# Lab_Controller_Board_v05.net
KiCad netlist of a schematic drawn in EAGLE
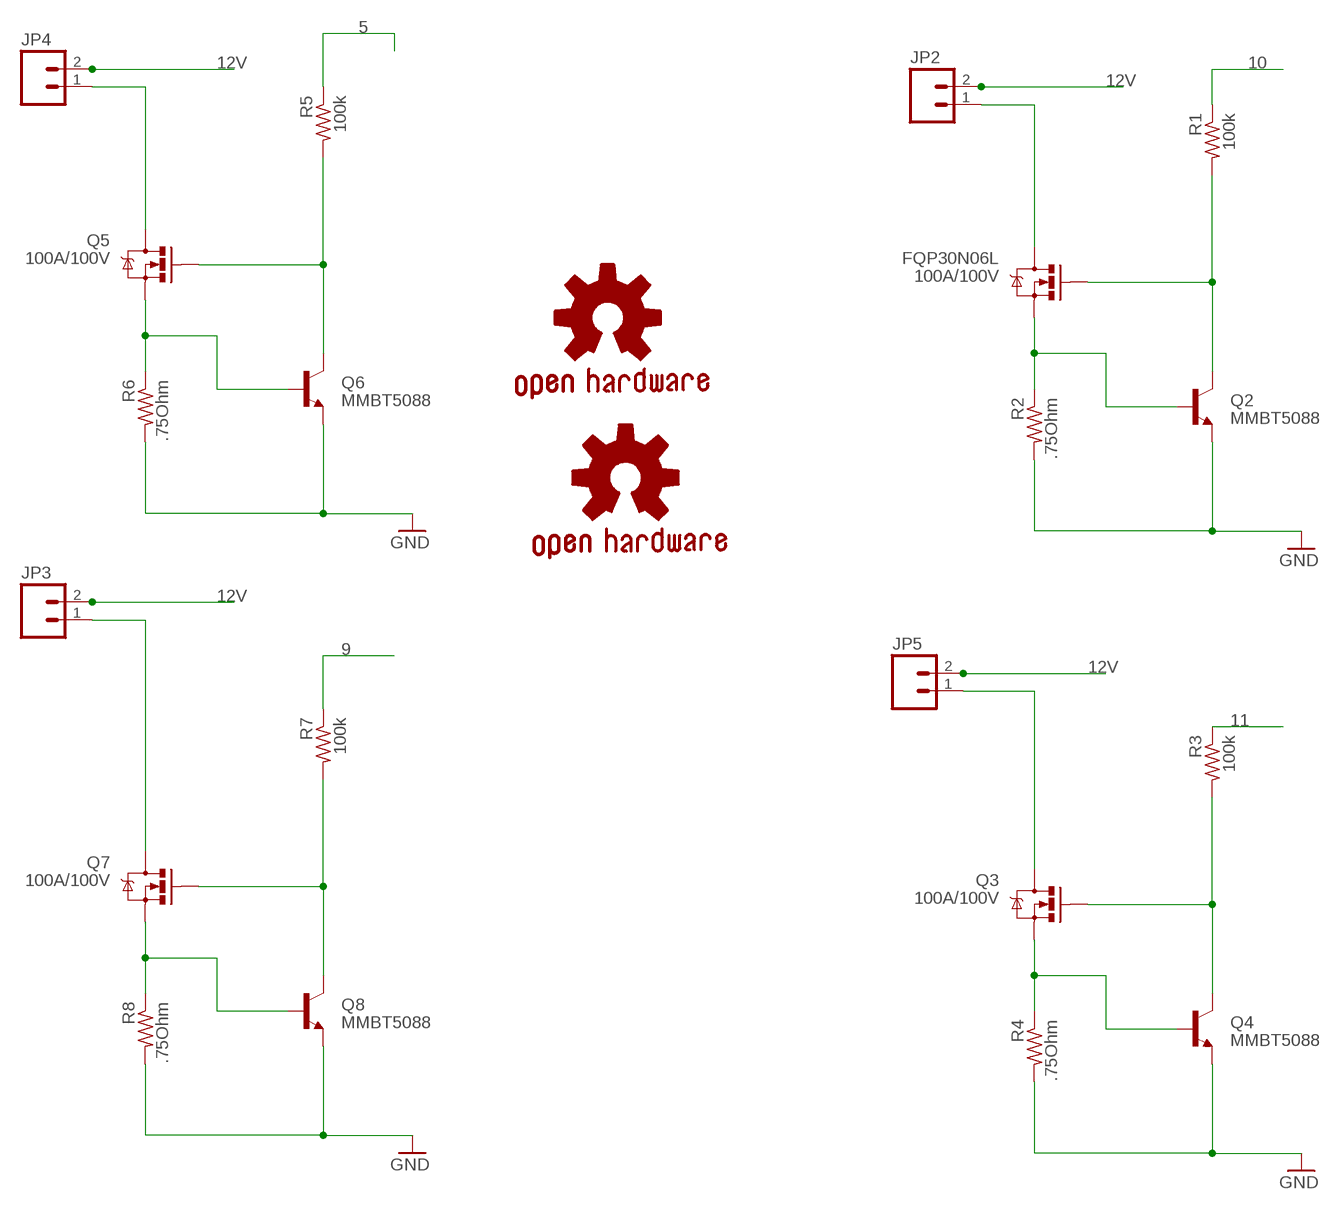
[diagram p0: schematic, sheet 1]
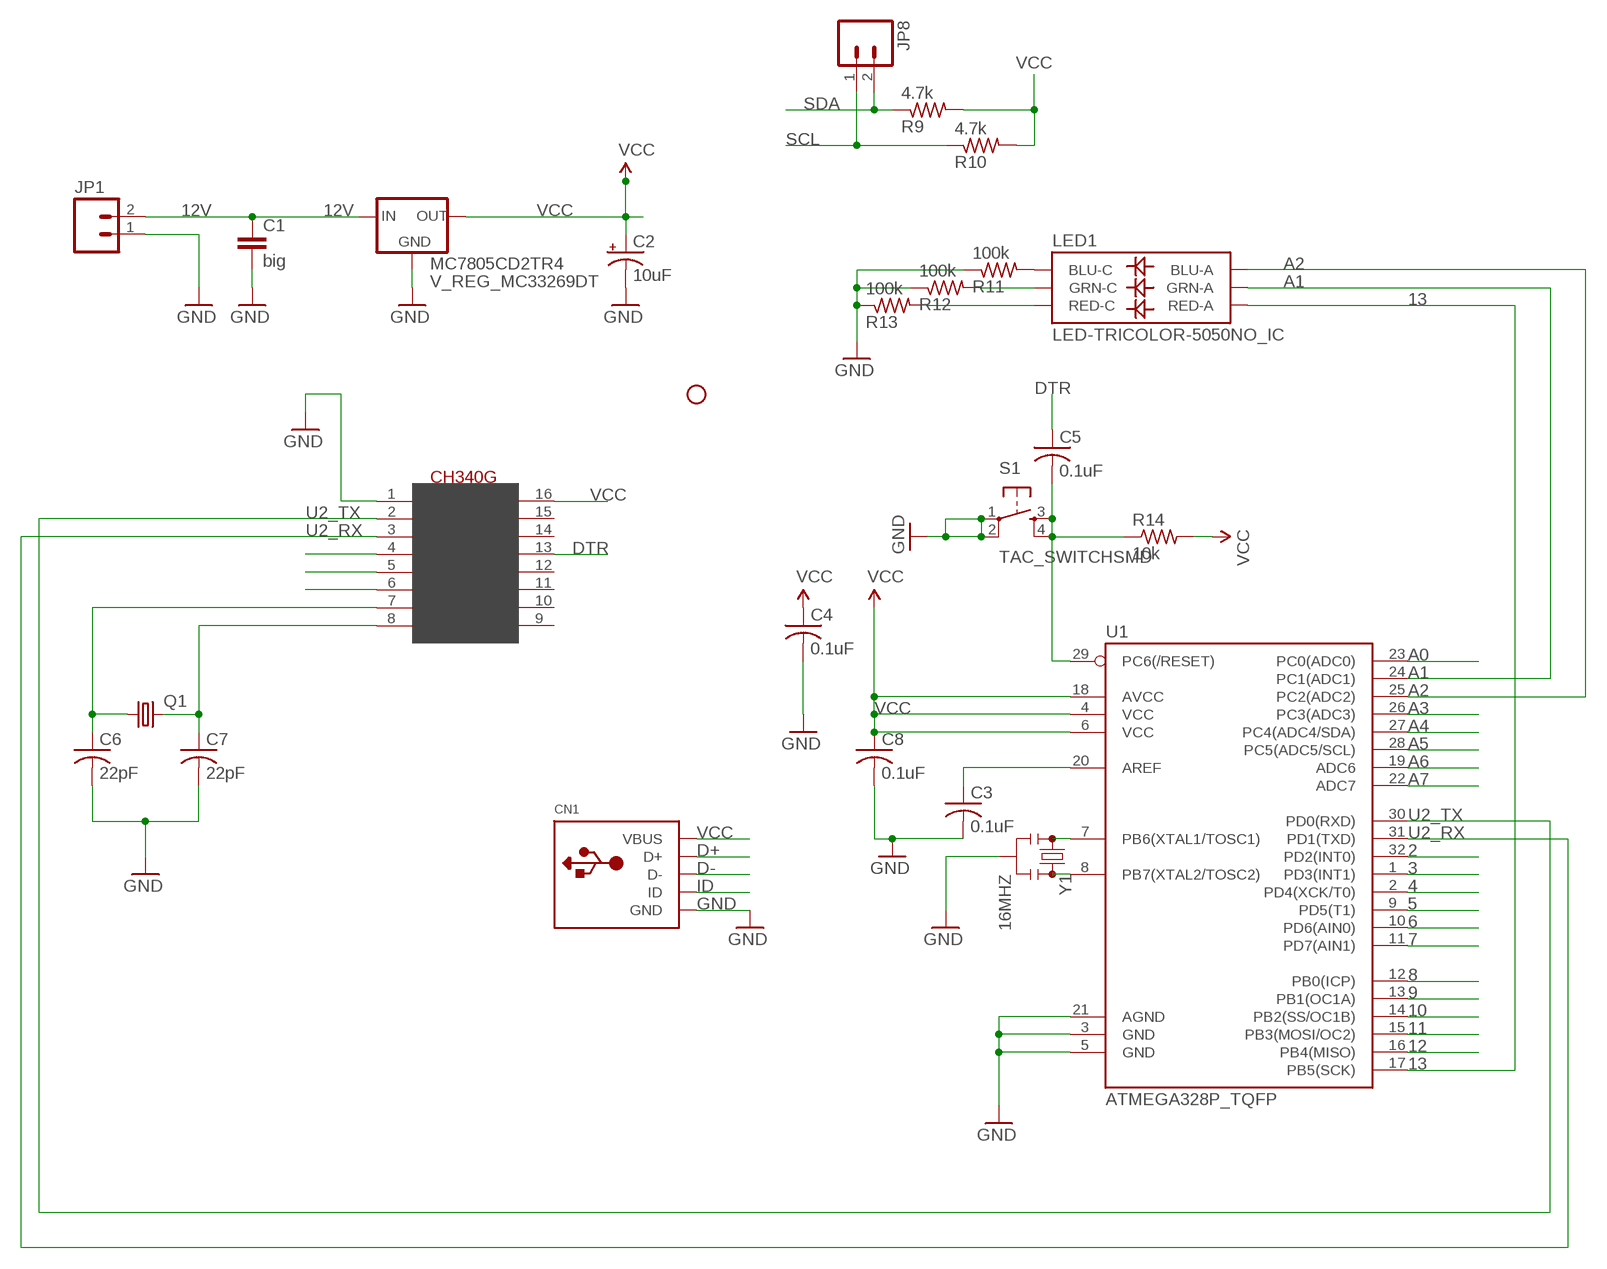
[diagram p1: schematic, sheet 2]

(export (version "E")
  (design (tool "Eeschema 10.0.6"))
  (components
    (comp (ref "FQP30N06L")
      (value "100A/100V")
      (footprint "eagle-import:TO-263_D2PAK")
      (libsource (lib "eagle-import") (part "MOSFET-NCHANNELPSMN7R0"))
    )
    (comp (ref "GOLD_ORB_SM1")
      (value "OSHWLOGO_GOLD_ORB_MED")
      (footprint "eagle-import:OSHW1")
      (libsource (lib "eagle-import") (part "OSHWLOGO_GOLD_ORB_MED"))
    )
    (comp (ref "GOLD_ORB_SM2")
      (value "OSHWLOGO_GOLD_ORB_SM")
      (footprint "eagle-import:OSHW2")
      (libsource (lib "eagle-import") (part "OSHWLOGO_GOLD_ORB_SM"))
    )
    (comp (ref "JP2")
      (value "M025MM")
      (footprint "eagle-import:SCREWTERMINAL-5MM-2")
      (libsource (lib "eagle-import") (part "M025MM"))
    )
    (comp (ref "JP3")
      (value "M025MM")
      (footprint "eagle-import:SCREWTERMINAL-5MM-2")
      (libsource (lib "eagle-import") (part "M025MM"))
    )
    (comp (ref "JP4")
      (value "M025MM")
      (footprint "eagle-import:SCREWTERMINAL-5MM-2")
      (libsource (lib "eagle-import") (part "M025MM"))
    )
    (comp (ref "JP5")
      (value "M025MM")
      (footprint "eagle-import:SCREWTERMINAL-5MM-2")
      (libsource (lib "eagle-import") (part "M025MM"))
    )
    (comp (ref "Q2")
      (value "MMBT5088")
      (footprint "eagle-import:SOT23-3")
      (libsource (lib "eagle-import") (part "TRANSISTOR_NPNMMBT5088"))
    )
    (comp (ref "Q3")
      (value "100A/100V")
      (footprint "eagle-import:TO-263_D2PAK")
      (libsource (lib "eagle-import") (part "MOSFET-NCHANNELPSMN7R0"))
    )
    (comp (ref "Q4")
      (value "MMBT5088")
      (footprint "eagle-import:SOT23-3")
      (libsource (lib "eagle-import") (part "TRANSISTOR_NPNMMBT5088"))
    )
    (comp (ref "Q5")
      (value "100A/100V")
      (footprint "eagle-import:TO-263_D2PAK")
      (libsource (lib "eagle-import") (part "MOSFET-NCHANNELPSMN7R0"))
    )
    (comp (ref "Q6")
      (value "MMBT5088")
      (footprint "eagle-import:SOT23-3")
      (libsource (lib "eagle-import") (part "TRANSISTOR_NPNMMBT5088"))
    )
    (comp (ref "Q7")
      (value "100A/100V")
      (footprint "eagle-import:TO-263_D2PAK")
      (libsource (lib "eagle-import") (part "MOSFET-NCHANNELPSMN7R0"))
    )
    (comp (ref "Q8")
      (value "MMBT5088")
      (footprint "eagle-import:SOT23-3")
      (libsource (lib "eagle-import") (part "TRANSISTOR_NPNMMBT5088"))
    )
    (comp (ref "R1")
      (value "100k")
      (footprint "eagle-import:R0805W")
      (libsource (lib "eagle-import") (part "R-US_R0805W"))
    )
    (comp (ref "R2")
      (value ".75Ohm")
      (footprint "eagle-import:0411V")
      (libsource (lib "eagle-import") (part "R-US_0411/3V"))
    )
    (comp (ref "R3")
      (value "100k")
      (footprint "eagle-import:R0805W")
      (libsource (lib "eagle-import") (part "R-US_R0805W"))
    )
    (comp (ref "R4")
      (value ".75Ohm")
      (footprint "eagle-import:0411V")
      (libsource (lib "eagle-import") (part "R-US_0411/3V"))
    )
    (comp (ref "R5")
      (value "100k")
      (footprint "eagle-import:R0805W")
      (libsource (lib "eagle-import") (part "R-US_R0805W"))
    )
    (comp (ref "R6")
      (value ".75Ohm")
      (footprint "eagle-import:0411V")
      (libsource (lib "eagle-import") (part "R-US_0411/3V"))
    )
    (comp (ref "R7")
      (value "100k")
      (footprint "eagle-import:R0805W")
      (libsource (lib "eagle-import") (part "R-US_R0805W"))
    )
    (comp (ref "R8")
      (value ".75Ohm")
      (footprint "eagle-import:0411V")
      (libsource (lib "eagle-import") (part "R-US_0411/3V"))
    )
    (comp (ref "C1")
      (value "big")
      (footprint "eagle-import:CAP-PTH-5MM")
      (libsource (lib "eagle-import") (part "CAPPTH1"))
    )
    (comp (ref "C2")
      (value "10uF")
      (footprint "eagle-import:EIA3528")
      (libsource (lib "eagle-import") (part "CAP_POL3528"))
    )
    (comp (ref "C3")
      (value "0.1uF")
      (footprint "eagle-import:C0402")
      (libsource (lib "eagle-import") (part "C-USC0402"))
    )
    (comp (ref "C4")
      (value "0.1uF")
      (footprint "eagle-import:C0402")
      (libsource (lib "eagle-import") (part "C-USC0402"))
    )
    (comp (ref "C5")
      (value "0.1uF")
      (footprint "eagle-import:C0402")
      (libsource (lib "eagle-import") (part "C-USC0402"))
    )
    (comp (ref "C6")
      (value "22pF")
      (footprint "eagle-import:C0402")
      (libsource (lib "eagle-import") (part "C-USC0402"))
    )
    (comp (ref "C7")
      (value "22pF")
      (footprint "eagle-import:C0402")
      (libsource (lib "eagle-import") (part "C-USC0402"))
    )
    (comp (ref "C8")
      (value "0.1uF")
      (footprint "eagle-import:C0402")
      (libsource (lib "eagle-import") (part "C-USC0402"))
    )
    (comp (ref "CN1")
      (value "USBMINIB")
      (footprint "eagle-import:USB-MINIB")
      (libsource (lib "eagle-import") (part "USBMINIB"))
    )
    (comp (ref "JP1")
      (value "M025MM")
      (footprint "eagle-import:SCREWTERMINAL-5MM-2")
      (libsource (lib "eagle-import") (part "M025MM"))
    )
    (comp (ref "JP8")
      (value "M02LOCK")
      (footprint "eagle-import:1X02_LOCK")
      (libsource (lib "eagle-import") (part "M02LOCK"))
    )
    (comp (ref "LED1")
      (value "LED-TRICOLOR-5050NO_IC")
      (footprint "eagle-import:LED-TRICOLOR-5050")
      (libsource (lib "eagle-import") (part "LED-TRICOLOR-5050NO_IC"))
    )
    (comp (ref "MC7805CD2TR4")
      (value "V_REG_MC33269DT")
      (footprint "eagle-import:DPAK")
      (libsource (lib "eagle-import") (part "V_REG_MC33269DT"))
    )
    (comp (ref "Q1")
      (value "CRYSTALHC49UP")
      (footprint "eagle-import:HC49UP")
      (libsource (lib "eagle-import") (part "CRYSTALHC49UP"))
    )
    (comp (ref "R9")
      (value "4.7k")
      (footprint "eagle-import:M0805")
      (libsource (lib "eagle-import") (part "R-US_M0805"))
    )
    (comp (ref "R10")
      (value "4.7k")
      (footprint "eagle-import:M0805")
      (libsource (lib "eagle-import") (part "R-US_M0805"))
    )
    (comp (ref "R11")
      (value "100k")
      (footprint "eagle-import:R0805W")
      (libsource (lib "eagle-import") (part "R-US_R0805W"))
    )
    (comp (ref "R12")
      (value "100k")
      (footprint "eagle-import:R0805W")
      (libsource (lib "eagle-import") (part "R-US_R0805W"))
    )
    (comp (ref "R13")
      (value "100k")
      (footprint "eagle-import:R0805W")
      (libsource (lib "eagle-import") (part "R-US_R0805W"))
    )
    (comp (ref "R14")
      (value "10k")
      (footprint "eagle-import:R0402")
      (libsource (lib "eagle-import") (part "R-US_R0402"))
    )
    (comp (ref "S1")
      (value "TAC_SWITCHSMD")
      (footprint "eagle-import:TACTILE-SWITCH-SMD")
      (libsource (lib "eagle-import") (part "TAC_SWITCHSMD"))
    )
    (comp (ref "STANDOFF1")
      (value "STAND-OFF")
      (footprint "eagle-import:STAND-OFF")
      (libsource (lib "eagle-import") (part "STAND-OFF"))
    )
    (comp (ref "U1")
      (value "ATMEGA328P_TQFP")
      (footprint "eagle-import:TQFP32-08")
      (libsource (lib "eagle-import") (part "ATMEGA328P_TQFP"))
    )
    (comp (ref "U2")
      (value "CH340G")
      (footprint "eagle-import:SOIC16")
      (libsource (lib "eagle-import") (part "CH340G"))
    )
    (comp (ref "Y1")
      (value "16MHZ")
      (footprint "eagle-import:RESONATOR-SMD")
      (libsource (lib "eagle-import") (part "RESONATOR16MHZ"))
    )
  )
  (nets
    (net (code "1") (name "2") (class "Default")
      (node (ref "U1") (pin "32") (pinfunction "PD2(INT0)_32") (pintype "bidirectional"))
    )
    (net (code "2") (name "3") (class "Default")
      (node (ref "U1") (pin "1") (pinfunction "PD3(INT1)_1") (pintype "bidirectional"))
    )
    (net (code "3") (name "4") (class "Default")
      (node (ref "U1") (pin "2") (pinfunction "PD4(XCK/T0)_2") (pintype "bidirectional"))
    )
    (net (code "4") (name "5") (class "Default")
      (node (ref "R5") (pin "1") (pinfunction "1_1") (pintype "passive"))
      (node (ref "U1") (pin "9") (pinfunction "PD5(T1)_9") (pintype "bidirectional"))
    )
    (net (code "5") (name "6") (class "Default")
      (node (ref "U1") (pin "10") (pinfunction "PD6(AIN0)_10") (pintype "bidirectional"))
    )
    (net (code "6") (name "7") (class "Default")
      (node (ref "U1") (pin "11") (pinfunction "PD7(AIN1)_11") (pintype "bidirectional"))
    )
    (net (code "7") (name "8") (class "Default")
      (node (ref "U1") (pin "12") (pinfunction "PB0(ICP)_12") (pintype "bidirectional"))
    )
    (net (code "8") (name "9") (class "Default")
      (node (ref "R7") (pin "1") (pinfunction "1_1") (pintype "passive"))
      (node (ref "U1") (pin "13") (pinfunction "PB1(OC1A)_13") (pintype "bidirectional"))
    )
    (net (code "9") (name "10") (class "Default")
      (node (ref "R1") (pin "1") (pinfunction "1_1") (pintype "passive"))
      (node (ref "U1") (pin "14") (pinfunction "PB2(SS/OC1B)_14") (pintype "bidirectional"))
    )
    (net (code "10") (name "11") (class "Default")
      (node (ref "R3") (pin "1") (pinfunction "1_1") (pintype "passive"))
      (node (ref "U1") (pin "15") (pinfunction "PB3(MOSI/OC2)_15") (pintype "bidirectional"))
    )
    (net (code "11") (name "12") (class "Default")
      (node (ref "U1") (pin "16") (pinfunction "PB4(MISO)_16") (pintype "bidirectional"))
    )
    (net (code "12") (name "12V") (class "Default")
      (node (ref "C1") (pin "1") (pinfunction "1_1") (pintype "passive"))
      (node (ref "JP1") (pin "2") (pinfunction "2_2") (pintype "passive"))
      (node (ref "JP2") (pin "2") (pinfunction "2_2") (pintype "passive"))
      (node (ref "JP3") (pin "2") (pinfunction "2_2") (pintype "passive"))
      (node (ref "JP4") (pin "2") (pinfunction "2_2") (pintype "passive"))
      (node (ref "JP5") (pin "2") (pinfunction "2_2") (pintype "passive"))
      (node (ref "MC7805CD2TR4") (pin "3") (pinfunction "IN_3") (pintype "input"))
    )
    (net (code "13") (name "13") (class "Default")
      (node (ref "LED1") (pin "2") (pinfunction "RED-A_2") (pintype "bidirectional"))
      (node (ref "U1") (pin "17") (pinfunction "PB5(SCK)_17") (pintype "bidirectional"))
    )
    (net (code "14") (name "A0") (class "Default")
      (node (ref "U1") (pin "23") (pinfunction "PC0(ADC0)_23") (pintype "bidirectional"))
    )
    (net (code "15") (name "A1") (class "Default")
      (node (ref "LED1") (pin "1") (pinfunction "GRN-A_1") (pintype "bidirectional"))
      (node (ref "U1") (pin "24") (pinfunction "PC1(ADC1)_24") (pintype "bidirectional"))
    )
    (net (code "16") (name "A2") (class "Default")
      (node (ref "LED1") (pin "3") (pinfunction "BLU-A_3") (pintype "bidirectional"))
      (node (ref "U1") (pin "25") (pinfunction "PC2(ADC2)_25") (pintype "bidirectional"))
    )
    (net (code "17") (name "A3") (class "Default")
      (node (ref "U1") (pin "26") (pinfunction "PC3(ADC3)_26") (pintype "bidirectional"))
    )
    (net (code "18") (name "A4") (class "Default")
      (node (ref "U1") (pin "27") (pinfunction "PC4(ADC4/SDA)_27") (pintype "bidirectional"))
    )
    (net (code "19") (name "A5") (class "Default")
      (node (ref "U1") (pin "28") (pinfunction "PC5(ADC5/SCL)_28") (pintype "bidirectional"))
    )
    (net (code "20") (name "A6") (class "Default")
      (node (ref "U1") (pin "19") (pinfunction "ADC6_19") (pintype "bidirectional"))
    )
    (net (code "21") (name "A7") (class "Default")
      (node (ref "U1") (pin "22") (pinfunction "ADC7_22") (pintype "bidirectional"))
    )
    (net (code "22") (name "D+") (class "Default")
      (node (ref "CN1") (pin "D+") (pinfunction "D+_D+") (pintype "bidirectional"))
      (node (ref "U2") (pin "5") (pinfunction "D+_5") (pintype "bidirectional"))
    )
    (net (code "23") (name "D-") (class "Default")
      (node (ref "CN1") (pin "D-") (pinfunction "D-_D-") (pintype "bidirectional"))
      (node (ref "U2") (pin "6") (pinfunction "D-_6") (pintype "bidirectional"))
    )
    (net (code "24") (name "DTR") (class "Default")
      (node (ref "C5") (pin "1") (pinfunction "1_1") (pintype "passive"))
      (node (ref "U2") (pin "13") (pinfunction "DTR_13") (pintype "bidirectional"))
    )
    (net (code "25") (name "GND") (class "Default")
      (node (ref "C1") (pin "2") (pinfunction "2_2") (pintype "passive"))
      (node (ref "C2") (pin "C") (pinfunction "-_C") (pintype "passive"))
      (node (ref "C3") (pin "2") (pinfunction "2_2") (pintype "passive"))
      (node (ref "C4") (pin "2") (pinfunction "2_2") (pintype "passive"))
      (node (ref "C6") (pin "2") (pinfunction "2_2") (pintype "passive"))
      (node (ref "C7") (pin "2") (pinfunction "2_2") (pintype "passive"))
      (node (ref "C8") (pin "2") (pinfunction "2_2") (pintype "passive"))
      (node (ref "CN1") (pin "GND") (pinfunction "GND_GND") (pintype "power_in"))
      (node (ref "JP1") (pin "1") (pinfunction "1_1") (pintype "passive"))
      (node (ref "MC7805CD2TR4") (pin "1") (pinfunction "GND_1") (pintype "input"))
      (node (ref "Q2") (pin "2") (pinfunction "E_2") (pintype "passive"))
      (node (ref "Q4") (pin "2") (pinfunction "E_2") (pintype "passive"))
      (node (ref "Q6") (pin "2") (pinfunction "E_2") (pintype "passive"))
      (node (ref "Q8") (pin "2") (pinfunction "E_2") (pintype "passive"))
      (node (ref "R11") (pin "1") (pinfunction "1_1") (pintype "passive"))
      (node (ref "R12") (pin "1") (pinfunction "1_1") (pintype "passive"))
      (node (ref "R13") (pin "1") (pinfunction "1_1") (pintype "passive"))
      (node (ref "R2") (pin "2") (pinfunction "2_2") (pintype "passive"))
      (node (ref "R4") (pin "2") (pinfunction "2_2") (pintype "passive"))
      (node (ref "R6") (pin "2") (pinfunction "2_2") (pintype "passive"))
      (node (ref "R8") (pin "2") (pinfunction "2_2") (pintype "passive"))
      (node (ref "S1") (pin "1") (pinfunction "1_1") (pintype "passive"))
      (node (ref "S1") (pin "2") (pinfunction "2_2") (pintype "passive"))
      (node (ref "U1") (pin "21") (pinfunction "AGND_21") (pintype "bidirectional"))
      (node (ref "U1") (pin "3") (pinfunction "GND_3") (pintype "bidirectional"))
      (node (ref "U1") (pin "5") (pinfunction "GND_5") (pintype "bidirectional"))
      (node (ref "U2") (pin "1") (pinfunction "GND_1") (pintype "bidirectional"))
      (node (ref "Y1") (pin "2") (pinfunction "2_2") (pintype "passive"))
    )
    (net (code "26") (name "ID") (class "Default")
      (node (ref "CN1") (pin "ID") (pinfunction "ID_ID") (pintype "bidirectional"))
    )
    (net (code "27") (name "Net-(FQP30N06L-D)") (class "Default")
      (node (ref "FQP30N06L") (pin "2") (pinfunction "D_2") (pintype "passive"))
      (node (ref "JP2") (pin "1") (pinfunction "1_1") (pintype "passive"))
    )
    (net (code "28") (name "Net-(FQP30N06L-G)") (class "Default")
      (node (ref "FQP30N06L") (pin "1") (pinfunction "G_1") (pintype "passive"))
      (node (ref "Q2") (pin "3") (pinfunction "C_3") (pintype "passive"))
      (node (ref "R1") (pin "2") (pinfunction "2_2") (pintype "passive"))
    )
    (net (code "29") (name "Net-(FQP30N06L-S)") (class "Default")
      (node (ref "FQP30N06L") (pin "3") (pinfunction "S_3") (pintype "passive"))
      (node (ref "Q2") (pin "1") (pinfunction "B_1") (pintype "passive"))
      (node (ref "R2") (pin "1") (pinfunction "1_1") (pintype "passive"))
    )
    (net (code "30") (name "Net-(LED1-BLU-C)") (class "Default")
      (node (ref "LED1") (pin "4") (pinfunction "BLU-C_4") (pintype "bidirectional"))
      (node (ref "R11") (pin "2") (pinfunction "2_2") (pintype "passive"))
    )
    (net (code "31") (name "Net-(LED1-GRN-C)") (class "Default")
      (node (ref "LED1") (pin "6") (pinfunction "GRN-C_6") (pintype "bidirectional"))
      (node (ref "R12") (pin "2") (pinfunction "2_2") (pintype "passive"))
    )
    (net (code "32") (name "Net-(LED1-RED-C)") (class "Default")
      (node (ref "LED1") (pin "5") (pinfunction "RED-C_5") (pintype "bidirectional"))
      (node (ref "R13") (pin "2") (pinfunction "2_2") (pintype "passive"))
    )
    (net (code "33") (name "Net-(Q3-D)") (class "Default")
      (node (ref "JP5") (pin "1") (pinfunction "1_1") (pintype "passive"))
      (node (ref "Q3") (pin "2") (pinfunction "D_2") (pintype "passive"))
    )
    (net (code "34") (name "Net-(Q3-G)") (class "Default")
      (node (ref "Q3") (pin "1") (pinfunction "G_1") (pintype "passive"))
      (node (ref "Q4") (pin "3") (pinfunction "C_3") (pintype "passive"))
      (node (ref "R3") (pin "2") (pinfunction "2_2") (pintype "passive"))
    )
    (net (code "35") (name "Net-(Q3-S)") (class "Default")
      (node (ref "Q3") (pin "3") (pinfunction "S_3") (pintype "passive"))
      (node (ref "Q4") (pin "1") (pinfunction "B_1") (pintype "passive"))
      (node (ref "R4") (pin "1") (pinfunction "1_1") (pintype "passive"))
    )
    (net (code "36") (name "Net-(Q5-D)") (class "Default")
      (node (ref "JP4") (pin "1") (pinfunction "1_1") (pintype "passive"))
      (node (ref "Q5") (pin "2") (pinfunction "D_2") (pintype "passive"))
    )
    (net (code "37") (name "Net-(Q5-G)") (class "Default")
      (node (ref "Q5") (pin "1") (pinfunction "G_1") (pintype "passive"))
      (node (ref "Q6") (pin "3") (pinfunction "C_3") (pintype "passive"))
      (node (ref "R5") (pin "2") (pinfunction "2_2") (pintype "passive"))
    )
    (net (code "38") (name "Net-(Q5-S)") (class "Default")
      (node (ref "Q5") (pin "3") (pinfunction "S_3") (pintype "passive"))
      (node (ref "Q6") (pin "1") (pinfunction "B_1") (pintype "passive"))
      (node (ref "R6") (pin "1") (pinfunction "1_1") (pintype "passive"))
    )
    (net (code "39") (name "Net-(Q7-D)") (class "Default")
      (node (ref "JP3") (pin "1") (pinfunction "1_1") (pintype "passive"))
      (node (ref "Q7") (pin "2") (pinfunction "D_2") (pintype "passive"))
    )
    (net (code "40") (name "Net-(Q7-G)") (class "Default")
      (node (ref "Q7") (pin "1") (pinfunction "G_1") (pintype "passive"))
      (node (ref "Q8") (pin "3") (pinfunction "C_3") (pintype "passive"))
      (node (ref "R7") (pin "2") (pinfunction "2_2") (pintype "passive"))
    )
    (net (code "41") (name "Net-(Q7-S)") (class "Default")
      (node (ref "Q7") (pin "3") (pinfunction "S_3") (pintype "passive"))
      (node (ref "Q8") (pin "1") (pinfunction "B_1") (pintype "passive"))
      (node (ref "R8") (pin "1") (pinfunction "1_1") (pintype "passive"))
    )
    (net (code "42") (name "Net-(U1-AREF)") (class "Default")
      (node (ref "C3") (pin "1") (pinfunction "1_1") (pintype "passive"))
      (node (ref "U1") (pin "20") (pinfunction "AREF_20") (pintype "bidirectional"))
    )
    (net (code "43") (name "Net-(U1-PB6(XTAL1{slash}TOSC1))") (class "Default")
      (node (ref "U1") (pin "7") (pinfunction "PB6(XTAL1/TOSC1)_7") (pintype "bidirectional"))
      (node (ref "Y1") (pin "1") (pinfunction "1_1") (pintype "passive"))
    )
    (net (code "44") (name "Net-(U1-PB7(XTAL2{slash}TOSC2))") (class "Default")
      (node (ref "U1") (pin "8") (pinfunction "PB7(XTAL2/TOSC2)_8") (pintype "bidirectional"))
      (node (ref "Y1") (pin "3") (pinfunction "3_3") (pintype "passive"))
    )
    (net (code "45") (name "Net-(U1-PC6({slash}RESET))") (class "Default")
      (node (ref "C5") (pin "2") (pinfunction "2_2") (pintype "passive"))
      (node (ref "R14") (pin "1") (pinfunction "1_1") (pintype "passive"))
      (node (ref "S1") (pin "3") (pinfunction "3_3") (pintype "passive"))
      (node (ref "S1") (pin "4") (pinfunction "4_4") (pintype "passive"))
      (node (ref "U1") (pin "29") (pinfunction "PC6(/RESET)_29") (pintype "bidirectional"))
    )
    (net (code "46") (name "Net-(U2-XI)") (class "Default")
      (node (ref "C6") (pin "1") (pinfunction "1_1") (pintype "passive"))
      (node (ref "Q1") (pin "1") (pinfunction "1_1") (pintype "passive"))
      (node (ref "U2") (pin "7") (pinfunction "XI_7") (pintype "bidirectional"))
    )
    (net (code "47") (name "Net-(U2-XO)") (class "Default")
      (node (ref "C7") (pin "1") (pinfunction "1_1") (pintype "passive"))
      (node (ref "Q1") (pin "2") (pinfunction "2_2") (pintype "passive"))
      (node (ref "U2") (pin "8") (pinfunction "XO_8") (pintype "bidirectional"))
    )
    (net (code "48") (name "SCL") (class "Default")
      (node (ref "JP8") (pin "1") (pinfunction "1_1") (pintype "passive"))
      (node (ref "R10") (pin "1") (pinfunction "1_1") (pintype "passive"))
    )
    (net (code "49") (name "SDA") (class "Default")
      (node (ref "JP8") (pin "2") (pinfunction "2_2") (pintype "passive"))
      (node (ref "R9") (pin "1") (pinfunction "1_1") (pintype "passive"))
    )
    (net (code "50") (name "U2_RX") (class "Default")
      (node (ref "U1") (pin "31") (pinfunction "PD1(TXD)_31") (pintype "bidirectional"))
      (node (ref "U2") (pin "3") (pinfunction "RX_3") (pintype "bidirectional"))
    )
    (net (code "51") (name "U2_TX") (class "Default")
      (node (ref "U1") (pin "30") (pinfunction "PD0(RXD)_30") (pintype "bidirectional"))
      (node (ref "U2") (pin "2") (pinfunction "TX_2") (pintype "bidirectional"))
    )
    (net (code "52") (name "VCC") (class "Default")
      (node (ref "C2") (pin "A") (pinfunction "+_A") (pintype "passive"))
      (node (ref "C4") (pin "1") (pinfunction "1_1") (pintype "passive"))
      (node (ref "C8") (pin "1") (pinfunction "1_1") (pintype "passive"))
      (node (ref "CN1") (pin "VBUS") (pinfunction "VBUS_VBUS") (pintype "power_in"))
      (node (ref "MC7805CD2TR4") (pin "4") (pinfunction "OUT_4") (pintype "passive"))
      (node (ref "R10") (pin "2") (pinfunction "2_2") (pintype "passive"))
      (node (ref "R14") (pin "2") (pinfunction "2_2") (pintype "passive"))
      (node (ref "R9") (pin "2") (pinfunction "2_2") (pintype "passive"))
      (node (ref "U1") (pin "18") (pinfunction "AVCC_18") (pintype "bidirectional"))
      (node (ref "U1") (pin "4") (pinfunction "VCC_4") (pintype "bidirectional"))
      (node (ref "U1") (pin "6") (pinfunction "VCC_6") (pintype "bidirectional"))
      (node (ref "U2") (pin "16") (pinfunction "VCC_16") (pintype "bidirectional"))
    )
    (net (code "53") (name "unconnected-(U2-CTS-Pad9)") (class "Default")
      (node (ref "U2") (pin "9") (pinfunction "CTS_9") (pintype "bidirectional"))
    )
    (net (code "54") (name "unconnected-(U2-DCD-Pad12)") (class "Default")
      (node (ref "U2") (pin "12") (pinfunction "DCD_12") (pintype "bidirectional"))
    )
    (net (code "55") (name "unconnected-(U2-DSR-Pad10)") (class "Default")
      (node (ref "U2") (pin "10") (pinfunction "DSR_10") (pintype "bidirectional"))
    )
    (net (code "56") (name "unconnected-(U2-RI-Pad11)") (class "Default")
      (node (ref "U2") (pin "11") (pinfunction "RI_11") (pintype "bidirectional"))
    )
    (net (code "57") (name "unconnected-(U2-RS232-Pad15)") (class "Default")
      (node (ref "U2") (pin "15") (pinfunction "RS232_15") (pintype "bidirectional"))
    )
    (net (code "58") (name "unconnected-(U2-RTS-Pad14)") (class "Default")
      (node (ref "U2") (pin "14") (pinfunction "RTS_14") (pintype "bidirectional"))
    )
    (net (code "59") (name "unconnected-(U2-V3-Pad4)") (class "Default")
      (node (ref "U2") (pin "4") (pinfunction "V3_4") (pintype "bidirectional"))
    )
  )
)
